# synth-zodiac-virgo-lfo.net
KiCad netlist of a schematic drawn in EAGLE
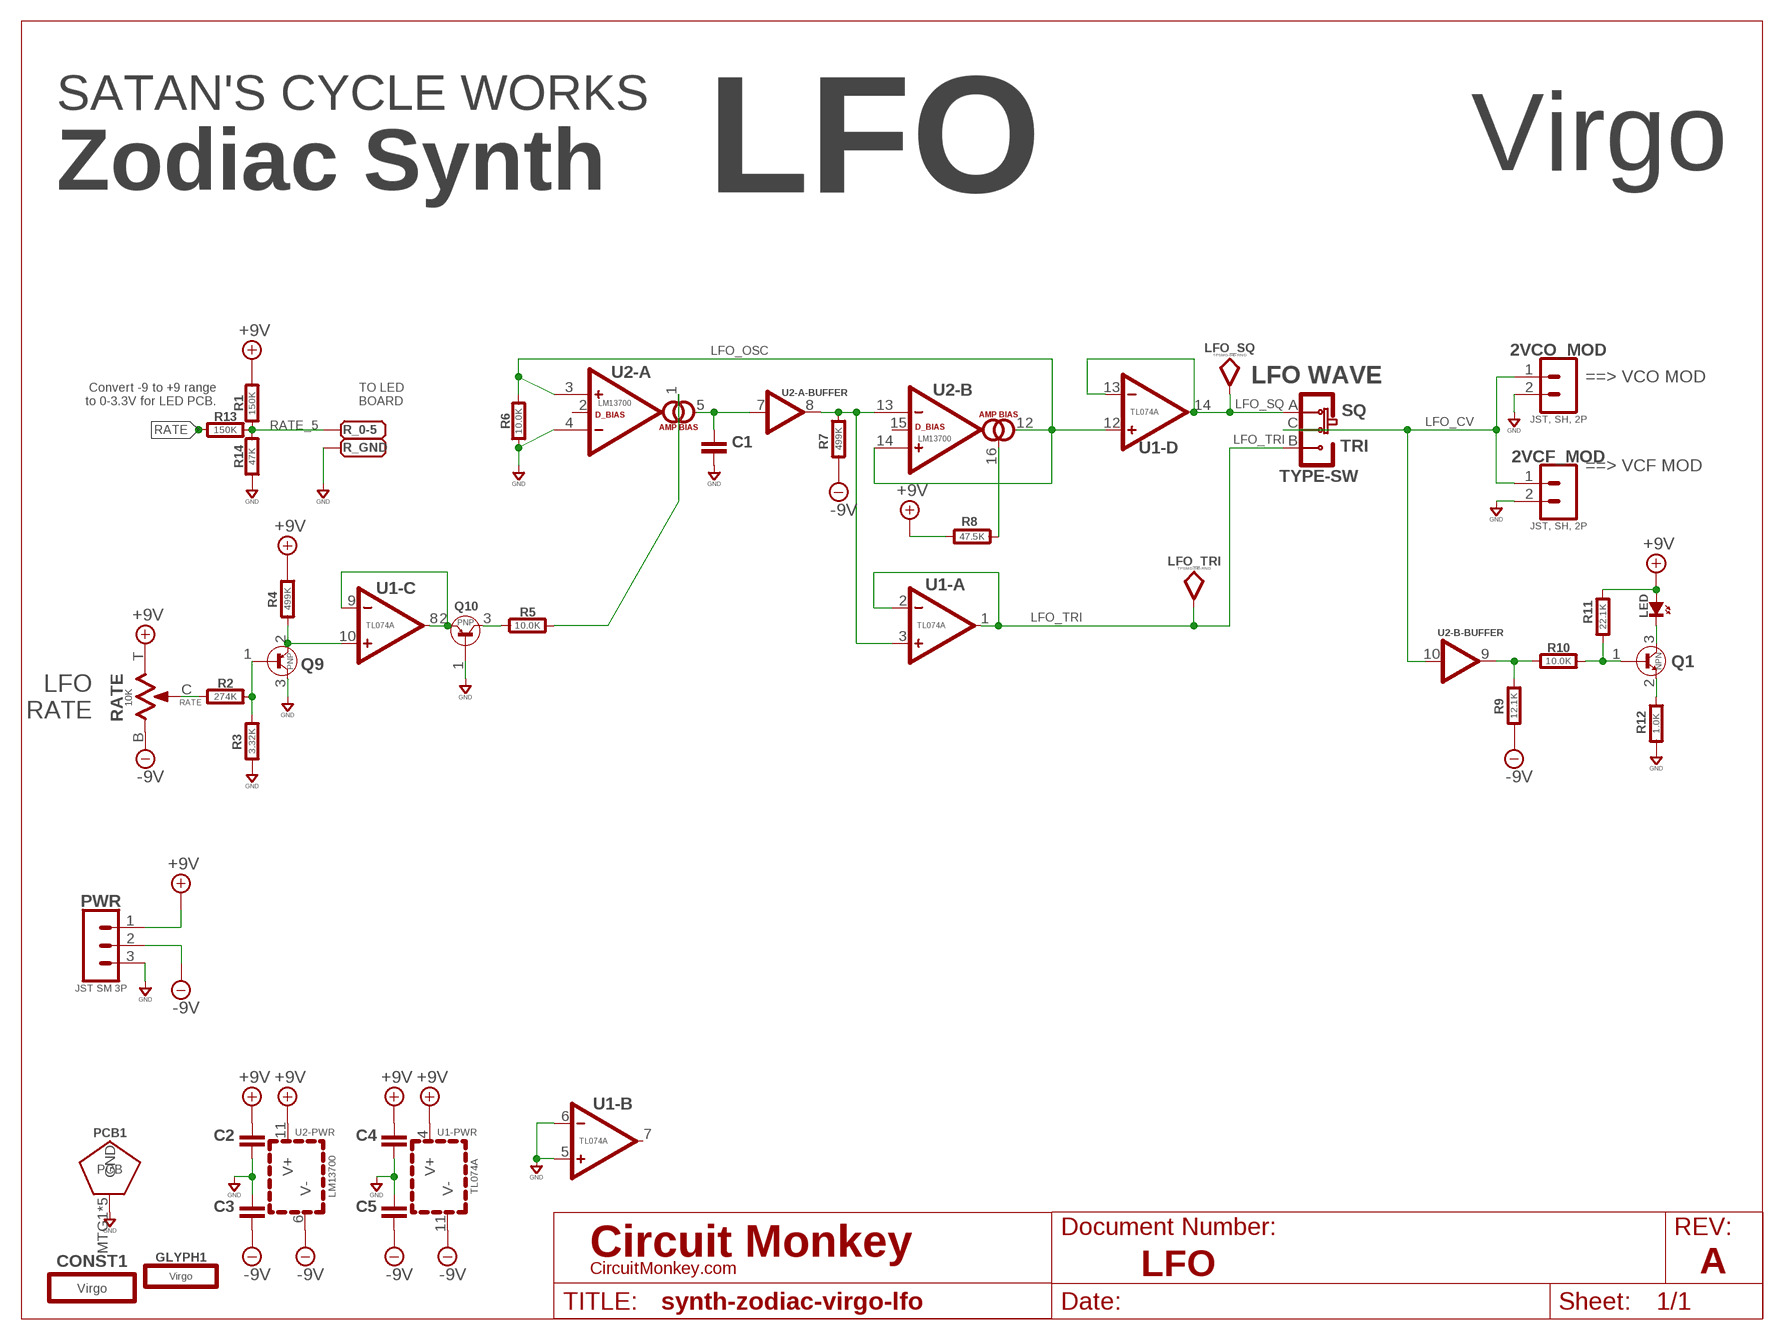
[diagram p0: schematic, sheet 1]

(export (version "E")
  (design (tool "Eeschema 10.0.6"))
  (components
    (comp (ref "2VCF_MOD")
      (value "JST, SH, 2P")
      (footprint "eagle-import:BM02B-SRSS-TB")
      (fields (field (name "MFR") "JST") (field (name "MPN") "BMB02B-SRSS-TB"))
      (libsource (lib "eagle-import") (part "02P-SM-VT-SMT"))
    )
    (comp (ref "2VCO_MOD")
      (value "JST, SH, 2P")
      (footprint "eagle-import:BM02B-SRSS-TB")
      (fields (field (name "MFR") "JST") (field (name "MPN") "BMB02B-SRSS-TB"))
      (libsource (lib "eagle-import") (part "02P-SM-VT-SMT"))
    )
    (comp (ref "C1")
      (value "0.1uF")
      (footprint "eagle-import:0603-CAP")
      (libsource (lib "eagle-import") (part "CAPACITOR0603"))
    )
    (comp (ref "C2")
      (value "0.1uF")
      (footprint "eagle-import:0603-CAP")
      (libsource (lib "eagle-import") (part "CAPACITOR0603"))
    )
    (comp (ref "C3")
      (value "0.1uF")
      (footprint "eagle-import:0603-CAP")
      (libsource (lib "eagle-import") (part "CAPACITOR0603"))
    )
    (comp (ref "C4")
      (value "0.1uF")
      (footprint "eagle-import:0603-CAP")
      (libsource (lib "eagle-import") (part "CAPACITOR0603"))
    )
    (comp (ref "C5")
      (value "0.1uF")
      (footprint "eagle-import:0603-CAP")
      (libsource (lib "eagle-import") (part "CAPACITOR0603"))
    )
    (comp (ref "CONST1")
      (value "Virgo")
      (footprint "eagle-import:VIRGO-CONST")
      (libsource (lib "eagle-import") (part "CONSTELLATION-VIRGO"))
    )
    (comp (ref "GLYPH1")
      (value "Virgo")
      (footprint "eagle-import:VIRGO-GLYPH")
      (libsource (lib "eagle-import") (part "GLYPH-VIRGO"))
    )
    (comp (ref "LED")
      (value "BLU")
      (footprint "eagle-import:SMD_0603")
      (libsource (lib "eagle-import") (part "SMT0603"))
    )
    (comp (ref "LFO_SQ")
      (value "TPSMD-040-RND")
      (footprint "eagle-import:SMD-040MIL-RND")
      (libsource (lib "eagle-import") (part "TPSMD-040-RND"))
    )
    (comp (ref "LFO_TRI")
      (value "TPSMD-040-RND")
      (footprint "eagle-import:SMD-040MIL-RND")
      (libsource (lib "eagle-import") (part "TPSMD-040-RND"))
    )
    (comp (ref "PCB1")
      (value "PCB FAB")
      (footprint "eagle-import:PENTAGON-40MM-RAD")
      (libsource (lib "eagle-import") (part "PENTAGON-40R"))
    )
    (comp (ref "PWR")
      (value "JST SM 3P")
      (footprint "eagle-import:BM03B-SRSS-TB")
      (fields (field (name "MFR") "JST") (field (name "MPN") "BM03B-SRSS-TB"))
      (libsource (lib "eagle-import") (part "03P-SM-VT-SMT"))
    )
    (comp (ref "Q1")
      (value "NPN")
      (footprint "eagle-import:SOT-23")
      (fields (field (name "MFR") "On Semiconductor") (field (name "MPN") "BC846"))
      (libsource (lib "eagle-import") (part "NPN-BC846"))
    )
    (comp (ref "Q9")
      (value "PNP")
      (footprint "eagle-import:SOT-23")
      (fields (field (name "MFR") "On Semiconductor") (field (name "MPN") "BC856"))
      (libsource (lib "eagle-import") (part "PNP-BC856"))
    )
    (comp (ref "Q10")
      (value "PNP")
      (footprint "eagle-import:SOT-23")
      (fields (field (name "MFR") "On Semiconductor") (field (name "MPN") "BC856"))
      (libsource (lib "eagle-import") (part "PNP-BC856"))
    )
    (comp (ref "R1")
      (value "150K")
      (footprint "eagle-import:0603-RES")
      (libsource (lib "eagle-import") (part "RESISTOR0603"))
    )
    (comp (ref "R2")
      (value "274K")
      (footprint "eagle-import:0603-RES")
      (libsource (lib "eagle-import") (part "RESISTOR0603"))
    )
    (comp (ref "R3")
      (value "3.32K")
      (footprint "eagle-import:0603-RES")
      (libsource (lib "eagle-import") (part "RESISTOR0603"))
    )
    (comp (ref "R4")
      (value "499K")
      (footprint "eagle-import:0603-RES")
      (libsource (lib "eagle-import") (part "RESISTOR0603"))
    )
    (comp (ref "R5")
      (value "10.0K")
      (footprint "eagle-import:0603-RES")
      (libsource (lib "eagle-import") (part "RESISTOR0603"))
    )
    (comp (ref "R6")
      (value "10.0K")
      (footprint "eagle-import:0603-RES")
      (libsource (lib "eagle-import") (part "RESISTOR0603"))
    )
    (comp (ref "R7")
      (value "499K")
      (footprint "eagle-import:0603-RES")
      (libsource (lib "eagle-import") (part "RESISTOR0603"))
    )
    (comp (ref "R8")
      (value "47.5K")
      (footprint "eagle-import:0603-RES")
      (libsource (lib "eagle-import") (part "RESISTOR0603"))
    )
    (comp (ref "R9")
      (value "12.1K")
      (footprint "eagle-import:0603-RES")
      (libsource (lib "eagle-import") (part "RESISTOR0603"))
    )
    (comp (ref "R10")
      (value "10.0K")
      (footprint "eagle-import:0603-RES")
      (libsource (lib "eagle-import") (part "RESISTOR0603"))
    )
    (comp (ref "R11")
      (value "22.1K")
      (footprint "eagle-import:0603-RES")
      (libsource (lib "eagle-import") (part "RESISTOR0603"))
    )
    (comp (ref "R12")
      (value "1.0K")
      (footprint "eagle-import:0603-RES")
      (libsource (lib "eagle-import") (part "RESISTOR0603"))
    )
    (comp (ref "R13")
      (value "150K")
      (footprint "eagle-import:0603-RES")
      (libsource (lib "eagle-import") (part "RESISTOR0603"))
    )
    (comp (ref "R14")
      (value "47K")
      (footprint "eagle-import:0603-RES")
      (libsource (lib "eagle-import") (part "RESISTOR0603"))
    )
    (comp (ref "RATE")
      (value "10K")
      (footprint "eagle-import:POT-RV9110")
      (fields (field (name "MFR") "Tayda") (field (name "MPN") "RV9110NO-OS15A00"))
      (libsource (lib "eagle-import") (part "TRIMPOT9MM_PCB_SHAFT"))
    )
    (comp (ref "R_0-5")
      (value "PADSMD-070X070")
      (footprint "eagle-import:SMD-070MIL")
      (libsource (lib "eagle-import") (part "PADSMD-070X070"))
    )
    (comp (ref "R_GND")
      (value "PADSMD-070X070")
      (footprint "eagle-import:SMD-070MIL")
      (libsource (lib "eagle-import") (part "PADSMD-070X070"))
    )
    (comp (ref "TYPE")
      (value "SLIDE-SPDT-MNTSS-12-F45-TH-PCB-2")
      (footprint "eagle-import:SS-12-F45-PNL-SMT-2")
      (fields (field (name "MFR") "Tayda") (field (name "MPN") "A-659/A-5111/A-5104"))
      (libsource (lib "eagle-import") (part "SLIDE-SPDT-MNTSS-12-F45-TH-PCB-2"))
    )
    (comp (ref "U1")
      (value "TL074A")
      (footprint "eagle-import:SOP14")
      (fields (field (name "MFR") "ST") (field (name "MPN") "TL074ACDT"))
      (libsource (lib "eagle-import") (part "QUADTL074A-SOIC"))
    )
    (comp (ref "U2")
      (value "LM13700")
      (footprint "eagle-import:SO16")
      (fields (field (name "MFR") "TI") (field (name "MPN") "LM13700M"))
      (libsource (lib "eagle-import") (part "DUAL-BIASLM13700-SMD"))
    )
  )
  (nets
    (net (code "1") (name "+9V") (class "Default")
      (node (ref "C2") (pin "1") (pinfunction "1_1") (pintype "passive"))
      (node (ref "C4") (pin "1") (pinfunction "1_1") (pintype "passive"))
      (node (ref "LED") (pin "A") (pinfunction "A_A") (pintype "passive"))
      (node (ref "PWR") (pin "1") (pinfunction "1_1") (pintype "passive"))
      (node (ref "R1") (pin "2") (pinfunction "2_2") (pintype "passive"))
      (node (ref "R11") (pin "1") (pinfunction "1_1") (pintype "passive"))
      (node (ref "R4") (pin "1") (pinfunction "1_1") (pintype "passive"))
      (node (ref "R8") (pin "2") (pinfunction "2_2") (pintype "passive"))
      (node (ref "RATE") (pin "T") (pinfunction "3_T") (pintype "passive"))
      (node (ref "U1") (pin "4") (pinfunction "V+_4") (pintype "power_in"))
      (node (ref "U2") (pin "11") (pinfunction "V+_11") (pintype "power_in"))
    )
    (net (code "2") (name "-9V") (class "Default")
      (node (ref "C3") (pin "2") (pinfunction "2_2") (pintype "passive"))
      (node (ref "C5") (pin "2") (pinfunction "2_2") (pintype "passive"))
      (node (ref "PWR") (pin "2") (pinfunction "2_2") (pintype "passive"))
      (node (ref "R7") (pin "2") (pinfunction "2_2") (pintype "passive"))
      (node (ref "R9") (pin "2") (pinfunction "2_2") (pintype "passive"))
      (node (ref "RATE") (pin "B") (pinfunction "1_B") (pintype "passive"))
      (node (ref "U1") (pin "11") (pinfunction "V-_11") (pintype "power_in"))
      (node (ref "U2") (pin "6") (pinfunction "V-_6") (pintype "power_in"))
    )
    (net (code "3") (name "/LFO_CV") (class "Default")
      (node (ref "2VCF_MOD") (pin "1") (pinfunction "1_1") (pintype "passive"))
      (node (ref "2VCO_MOD") (pin "1") (pinfunction "1_1") (pintype "passive"))
      (node (ref "TYPE") (pin "C") (pinfunction "C_C") (pintype "bidirectional"))
      (node (ref "U2") (pin "10") (pinfunction "IN_10") (pintype "bidirectional"))
    )
    (net (code "4") (name "/LFO_OSC") (class "Default")
      (node (ref "R6") (pin "2") (pinfunction "2_2") (pintype "passive"))
      (node (ref "U1") (pin "12") (pinfunction "+_12") (pintype "input"))
      (node (ref "U2") (pin "12") (pinfunction "OUT_12") (pintype "output"))
      (node (ref "U2") (pin "14") (pinfunction "+_14") (pintype "input"))
      (node (ref "U2") (pin "3") (pinfunction "+_3") (pintype "input"))
    )
    (net (code "5") (name "/LFO_SQ") (class "Default")
      (node (ref "LFO_SQ") (pin "TP") (pinfunction "P$1_TP") (pintype "bidirectional"))
      (node (ref "TYPE") (pin "A") (pinfunction "A_A") (pintype "bidirectional"))
      (node (ref "U1") (pin "13") (pinfunction "-_13") (pintype "input"))
      (node (ref "U1") (pin "14") (pinfunction "OUT_14") (pintype "output"))
    )
    (net (code "6") (name "/LFO_TRI") (class "Default")
      (node (ref "LFO_TRI") (pin "TP") (pinfunction "P$1_TP") (pintype "bidirectional"))
      (node (ref "TYPE") (pin "B") (pinfunction "B_B") (pintype "bidirectional"))
      (node (ref "U1") (pin "1") (pinfunction "OUT_1") (pintype "output"))
      (node (ref "U1") (pin "2") (pinfunction "-_2") (pintype "input"))
    )
    (net (code "7") (name "/RATE_5") (class "Default")
      (node (ref "R1") (pin "1") (pinfunction "1_1") (pintype "passive"))
      (node (ref "R13") (pin "2") (pinfunction "2_2") (pintype "passive"))
      (node (ref "R14") (pin "2") (pinfunction "2_2") (pintype "passive"))
      (node (ref "R_0-5") (pin "1") (pinfunction "PAD_1") (pintype "bidirectional"))
    )
    (net (code "8") (name "GND") (class "Default")
      (node (ref "2VCF_MOD") (pin "2") (pinfunction "2_2") (pintype "passive"))
      (node (ref "2VCO_MOD") (pin "2") (pinfunction "2_2") (pintype "passive"))
      (node (ref "C1") (pin "2") (pinfunction "2_2") (pintype "passive"))
      (node (ref "C2") (pin "2") (pinfunction "2_2") (pintype "passive"))
      (node (ref "C3") (pin "1") (pinfunction "1_1") (pintype "passive"))
      (node (ref "C4") (pin "2") (pinfunction "2_2") (pintype "passive"))
      (node (ref "C5") (pin "1") (pinfunction "1_1") (pintype "passive"))
      (node (ref "PCB1") (pin "MTG1") (pinfunction "GND_MTG1") (pintype "bidirectional"))
      (node (ref "PCB1") (pin "MTG2") (pinfunction "GND_MTG2") (pintype "bidirectional"))
      (node (ref "PCB1") (pin "MTG3") (pinfunction "GND_MTG3") (pintype "bidirectional"))
      (node (ref "PCB1") (pin "MTG4") (pinfunction "GND_MTG4") (pintype "bidirectional"))
      (node (ref "PCB1") (pin "MTG5") (pinfunction "GND_MTG5") (pintype "bidirectional"))
      (node (ref "PWR") (pin "3") (pinfunction "3_3") (pintype "passive"))
      (node (ref "Q10") (pin "1") (pinfunction "BASE_1") (pintype "bidirectional"))
      (node (ref "Q9") (pin "3") (pinfunction "COLLECTOR_3") (pintype "bidirectional"))
      (node (ref "R12") (pin "2") (pinfunction "2_2") (pintype "passive"))
      (node (ref "R14") (pin "1") (pinfunction "1_1") (pintype "passive"))
      (node (ref "R3") (pin "2") (pinfunction "2_2") (pintype "passive"))
      (node (ref "R6") (pin "1") (pinfunction "1_1") (pintype "passive"))
      (node (ref "R_GND") (pin "1") (pinfunction "PAD_1") (pintype "bidirectional"))
      (node (ref "U1") (pin "5") (pinfunction "+_5") (pintype "input"))
      (node (ref "U1") (pin "6") (pinfunction "-_6") (pintype "input"))
      (node (ref "U2") (pin "4") (pinfunction "-_4") (pintype "input"))
    )
    (net (code "9") (name "Net-(LED-C)") (class "Default")
      (node (ref "LED") (pin "K") (pinfunction "C_K") (pintype "passive"))
      (node (ref "Q1") (pin "3") (pinfunction "COLLECTOR_3") (pintype "bidirectional"))
    )
    (net (code "10") (name "Net-(Q1-BASE)") (class "Default")
      (node (ref "Q1") (pin "1") (pinfunction "BASE_1") (pintype "bidirectional"))
      (node (ref "R10") (pin "2") (pinfunction "2_2") (pintype "passive"))
      (node (ref "R11") (pin "2") (pinfunction "2_2") (pintype "passive"))
    )
    (net (code "11") (name "Net-(Q1-EMITTER)") (class "Default")
      (node (ref "Q1") (pin "2") (pinfunction "EMITTER_2") (pintype "bidirectional"))
      (node (ref "R12") (pin "1") (pinfunction "1_1") (pintype "passive"))
    )
    (net (code "12") (name "Net-(Q9-BASE)") (class "Default")
      (node (ref "Q9") (pin "1") (pinfunction "BASE_1") (pintype "bidirectional"))
      (node (ref "R2") (pin "2") (pinfunction "2_2") (pintype "passive"))
      (node (ref "R3") (pin "1") (pinfunction "1_1") (pintype "passive"))
    )
    (net (code "13") (name "Net-(Q9-EMITTER)") (class "Default")
      (node (ref "Q9") (pin "2") (pinfunction "EMITTER_2") (pintype "bidirectional"))
      (node (ref "R4") (pin "2") (pinfunction "2_2") (pintype "passive"))
      (node (ref "U1") (pin "10") (pinfunction "+_10") (pintype "input"))
    )
    (net (code "14") (name "Net-(Q10-COLLECTOR)") (class "Default")
      (node (ref "Q10") (pin "3") (pinfunction "COLLECTOR_3") (pintype "bidirectional"))
      (node (ref "R5") (pin "1") (pinfunction "1_1") (pintype "passive"))
    )
    (net (code "15") (name "Net-(Q10-EMITTER)") (class "Default")
      (node (ref "Q10") (pin "2") (pinfunction "EMITTER_2") (pintype "bidirectional"))
      (node (ref "U1") (pin "8") (pinfunction "OUT_8") (pintype "output"))
      (node (ref "U1") (pin "9") (pinfunction "-_9") (pintype "input"))
    )
    (net (code "16") (name "Net-(U1A-+)") (class "Default")
      (node (ref "R7") (pin "1") (pinfunction "1_1") (pintype "passive"))
      (node (ref "U1") (pin "3") (pinfunction "+_3") (pintype "input"))
      (node (ref "U2") (pin "13") (pinfunction "-_13") (pintype "input"))
      (node (ref "U2") (pin "8") (pinfunction "OUT_8") (pintype "bidirectional"))
    )
    (net (code "17") (name "Net-(U2A-AMP-BIAS)") (class "Default")
      (node (ref "R5") (pin "2") (pinfunction "2_2") (pintype "passive"))
      (node (ref "U2") (pin "1") (pinfunction "AMP-BIAS_1") (pintype "passive"))
    )
    (net (code "18") (name "Net-(U2A-OUT)") (class "Default")
      (node (ref "C1") (pin "1") (pinfunction "1_1") (pintype "passive"))
      (node (ref "U2") (pin "5") (pinfunction "OUT_5") (pintype "output"))
      (node (ref "U2") (pin "7") (pinfunction "IN_7") (pintype "bidirectional"))
    )
    (net (code "19") (name "Net-(U2C-AMP-BIAS)") (class "Default")
      (node (ref "R8") (pin "1") (pinfunction "1_1") (pintype "passive"))
      (node (ref "U2") (pin "16") (pinfunction "AMP-BIAS_16") (pintype "passive"))
    )
    (net (code "20") (name "Net-(U2D-OUT)") (class "Default")
      (node (ref "R10") (pin "1") (pinfunction "1_1") (pintype "passive"))
      (node (ref "R9") (pin "1") (pinfunction "1_1") (pintype "passive"))
      (node (ref "U2") (pin "9") (pinfunction "OUT_9") (pintype "bidirectional"))
    )
    (net (code "21") (name "RATE") (class "Default")
      (node (ref "R13") (pin "1") (pinfunction "1_1") (pintype "passive"))
      (node (ref "R2") (pin "1") (pinfunction "1_1") (pintype "passive"))
      (node (ref "RATE") (pin "C") (pinfunction "2_C") (pintype "passive"))
    )
    (net (code "22") (name "unconnected-(U1B-OUT-Pad7)") (class "Default")
      (node (ref "U1") (pin "7") (pinfunction "OUT_7") (pintype "output"))
    )
    (net (code "23") (name "unconnected-(U2A-DIODE-BIAS-Pad2)") (class "Default")
      (node (ref "U2") (pin "2") (pinfunction "DIODE-BIAS_2") (pintype "bidirectional"))
    )
    (net (code "24") (name "unconnected-(U2C-DIODE-BIAS-Pad15)") (class "Default")
      (node (ref "U2") (pin "15") (pinfunction "DIODE-BIAS_15") (pintype "bidirectional"))
    )
  )
)
